# apex-alpha-ii.net
KiCad netlist of a schematic drawn in EAGLE
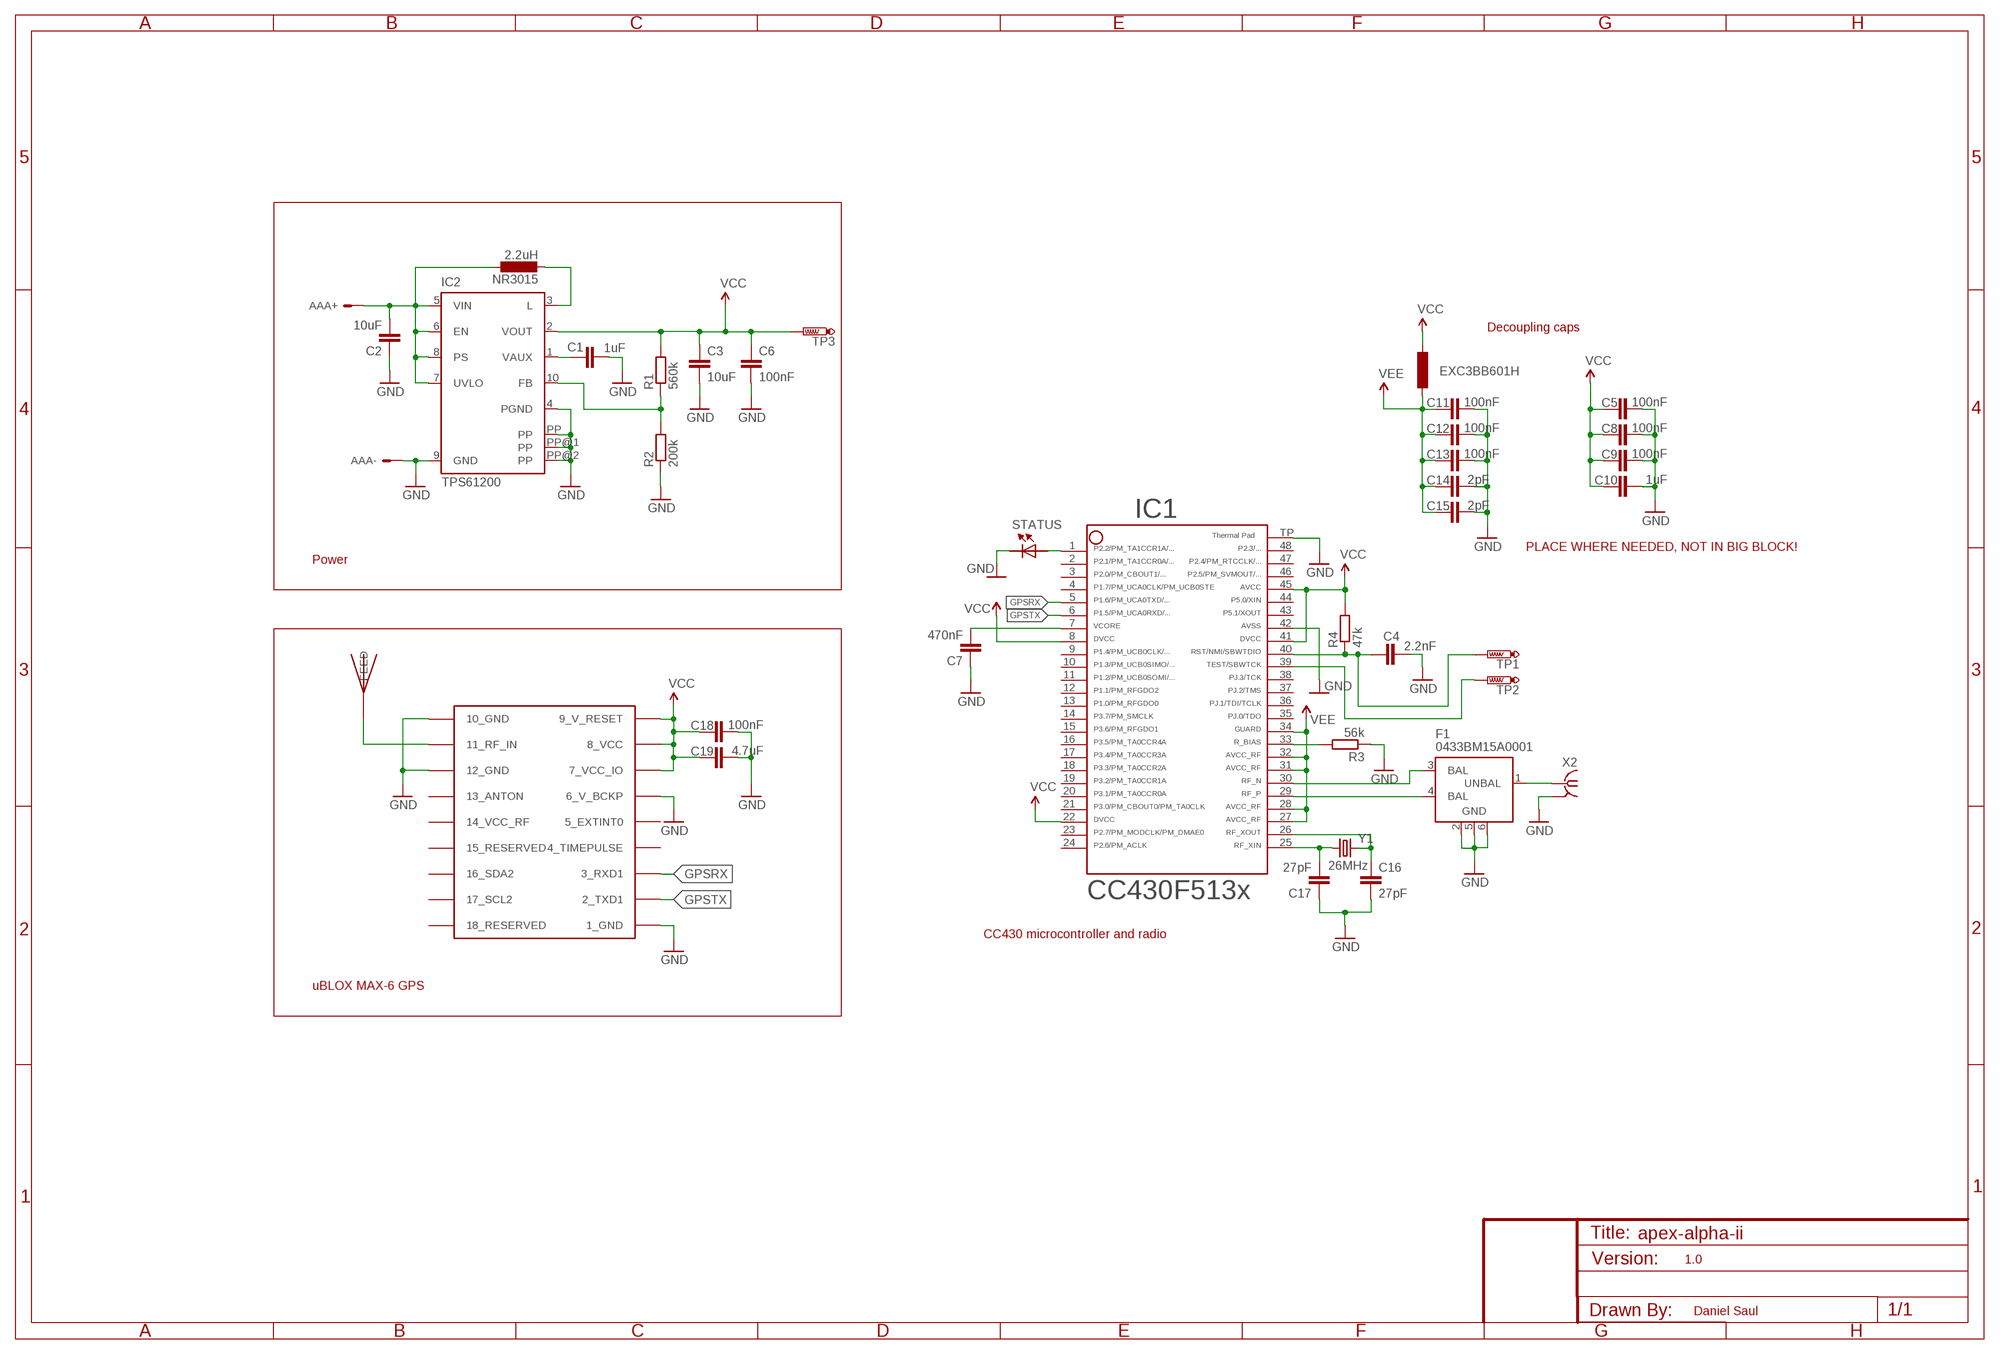
[diagram p0: schematic, sheet 1]

(export (version "E")
  (design (tool "Eeschema 10.0.6"))
  (components
    (comp (ref "AAA")
      (value "KEYSTONE-2466-THROUGH-HOLE-BATTERY-HOLDER-AAA")
      (footprint "eagle-import:THROUGH-HOLE-BATTERY-HOLDER-AAA")
      (libsource (lib "eagle-import") (part "KEYSTONE-2466-THROUGH-HOLE-BATTERY-HOLDER-AAA"))
    )
    (comp (ref "C1")
      (value "1uF")
      (footprint "eagle-import:0402-CAP")
      (libsource (lib "eagle-import") (part "CAP0402-CAP"))
    )
    (comp (ref "C2")
      (value "10uF")
      (footprint "eagle-import:0805")
      (libsource (lib "eagle-import") (part "CAP0805"))
    )
    (comp (ref "C3")
      (value "10uF")
      (footprint "eagle-import:0805")
      (libsource (lib "eagle-import") (part "CAP0805"))
    )
    (comp (ref "C4")
      (value "2.2nF")
      (footprint "eagle-import:0402-CAP")
      (libsource (lib "eagle-import") (part "CAP0402-CAP"))
    )
    (comp (ref "C5")
      (value "100nF")
      (footprint "eagle-import:0402-CAP")
      (libsource (lib "eagle-import") (part "CAP0402-CAP"))
    )
    (comp (ref "C6")
      (value "100nF")
      (footprint "eagle-import:0402-CAP")
      (libsource (lib "eagle-import") (part "CAP0402-CAP"))
    )
    (comp (ref "C7")
      (value "470nF")
      (footprint "eagle-import:0402-CAP")
      (libsource (lib "eagle-import") (part "CAP0402-CAP"))
    )
    (comp (ref "C8")
      (value "100nF")
      (footprint "eagle-import:0402-CAP")
      (libsource (lib "eagle-import") (part "CAP0402-CAP"))
    )
    (comp (ref "C9")
      (value "100nF")
      (footprint "eagle-import:0402-CAP")
      (libsource (lib "eagle-import") (part "CAP0402-CAP"))
    )
    (comp (ref "C10")
      (value "1uF")
      (footprint "eagle-import:0402-CAP")
      (libsource (lib "eagle-import") (part "CAP0402-CAP"))
    )
    (comp (ref "C11")
      (value "100nF")
      (footprint "eagle-import:0402-CAP")
      (libsource (lib "eagle-import") (part "CAP0402-CAP"))
    )
    (comp (ref "C12")
      (value "100nF")
      (footprint "eagle-import:0402-CAP")
      (libsource (lib "eagle-import") (part "CAP0402-CAP"))
    )
    (comp (ref "C13")
      (value "100nF")
      (footprint "eagle-import:0402-CAP")
      (libsource (lib "eagle-import") (part "CAP0402-CAP"))
    )
    (comp (ref "C14")
      (value "2pF")
      (footprint "eagle-import:0402-CAP")
      (libsource (lib "eagle-import") (part "CAP0402-CAP"))
    )
    (comp (ref "C15")
      (value "2pF")
      (footprint "eagle-import:0402-CAP")
      (libsource (lib "eagle-import") (part "CAP0402-CAP"))
    )
    (comp (ref "C16")
      (value "27pF")
      (footprint "eagle-import:0402-CAP")
      (libsource (lib "eagle-import") (part "CAP0402-CAP"))
    )
    (comp (ref "C17")
      (value "27pF")
      (footprint "eagle-import:0402-CAP")
      (libsource (lib "eagle-import") (part "CAP0402-CAP"))
    )
    (comp (ref "C18")
      (value "100nF")
      (footprint "eagle-import:0402-CAP")
      (libsource (lib "eagle-import") (part "CAP0402-CAP"))
    )
    (comp (ref "C19")
      (value "4.7uF")
      (footprint "eagle-import:0805")
      (libsource (lib "eagle-import") (part "CAP0805"))
    )
    (comp (ref "F1")
      (value "0433BM15A0001")
      (footprint "eagle-import:2450BM15A0002")
      (libsource (lib "eagle-import") (part "2450BM15A0002"))
    )
    (comp (ref "GPS")
      (value "UBLOX_MAX-6")
      (footprint "eagle-import:UBLOX_MAX-6")
      (libsource (lib "eagle-import") (part "UBLOX_MAX-6"))
    )
    (comp (ref "IC1")
      (value "CC430F5135")
      (footprint "eagle-import:RGZ48")
      (libsource (lib "eagle-import") (part "CC430F513X---RGZ48"))
    )
    (comp (ref "IC2")
      (value "TPS61200")
      (footprint "eagle-import:S-PDSO-N10")
      (fields (field (name "MPN") "TPS61200DRCT"))
      (libsource (lib "eagle-import") (part "TPS61200"))
    )
    (comp (ref "NR3015")
      (value "2.2uH")
      (footprint "eagle-import:NR3015")
      (libsource (lib "eagle-import") (part "NR3015"))
    )
    (comp (ref "R1")
      (value "560k")
      (footprint "eagle-import:R0402")
      (libsource (lib "eagle-import") (part "R-EU_R0402"))
    )
    (comp (ref "R2")
      (value "200k")
      (footprint "eagle-import:R0402")
      (libsource (lib "eagle-import") (part "R-EU_R0402"))
    )
    (comp (ref "R3")
      (value "56k")
      (footprint "eagle-import:R0402")
      (libsource (lib "eagle-import") (part "R-EU_R0402"))
    )
    (comp (ref "R4")
      (value "47k")
      (footprint "eagle-import:R0402")
      (libsource (lib "eagle-import") (part "R-EU_R0402"))
    )
    (comp (ref "TP1")
      (value "PTR1B1,27")
      (footprint "eagle-import:B1,27")
      (libsource (lib "eagle-import") (part "PTR1B1,27"))
    )
    (comp (ref "TP2")
      (value "PTR1B1,27")
      (footprint "eagle-import:B1,27")
      (libsource (lib "eagle-import") (part "PTR1B1,27"))
    )
    (comp (ref "TP3")
      (value "PTR1B1,27")
      (footprint "eagle-import:B1,27")
      (libsource (lib "eagle-import") (part "PTR1B1,27"))
    )
    (comp (ref "U$1")
      (value "JTI_ANTENNA-1575AT43A40")
      (footprint "eagle-import:JTI_ANTENNA-1575AT43A40")
      (libsource (lib "eagle-import") (part "JTI_ANTENNA-1575AT43A40"))
    )
    (comp (ref "U$2")
      (value "EXC3BB601H")
      (footprint "eagle-import:R0603")
      (libsource (lib "eagle-import") (part "0603INDUCTOR"))
    )
    (comp (ref "U$3")
      (value "STATUS")
      (footprint "eagle-import:R0402")
      (libsource (lib "eagle-import") (part "LED"))
    )
    (comp (ref "X2")
      (value "SMA-142-0701-801/806")
      (footprint "eagle-import:J502-ND-142-0701-801_806")
      (fields
        (field (name "MF") "JOHNSON COMPONENTS")
        (field (name "MPN") "142-0701-801")
        (field (name "MPN_1") "142-0701-801")
        (field (name "OC_FARNELL") "1608592")
        (field (name "OC_NEWARK") "90F2624")
      )
      (libsource (lib "eagle-import") (part "SMA-142-0701-801/806"))
    )
    (comp (ref "Y1")
      (value "26MHz")
      (footprint "eagle-import:CRYSTAL-SMD-5X3")
      (libsource (lib "eagle-import") (part "CRYSTAL5X3"))
    )
  )
  (nets
    (net (code "1") (name "GND") (class "Default")
      (node (ref "AAA") (pin "GND") (pinfunction "S_GND") (pintype "passive"))
      (node (ref "C1") (pin "2") (pinfunction "2_2") (pintype "passive"))
      (node (ref "C10") (pin "2") (pinfunction "2_2") (pintype "passive"))
      (node (ref "C11") (pin "2") (pinfunction "2_2") (pintype "passive"))
      (node (ref "C12") (pin "2") (pinfunction "2_2") (pintype "passive"))
      (node (ref "C13") (pin "2") (pinfunction "2_2") (pintype "passive"))
      (node (ref "C14") (pin "2") (pinfunction "2_2") (pintype "passive"))
      (node (ref "C15") (pin "2") (pinfunction "2_2") (pintype "passive"))
      (node (ref "C16") (pin "2") (pinfunction "2_2") (pintype "passive"))
      (node (ref "C17") (pin "1") (pinfunction "1_1") (pintype "passive"))
      (node (ref "C18") (pin "2") (pinfunction "2_2") (pintype "passive"))
      (node (ref "C19") (pin "2") (pinfunction "2_2") (pintype "passive"))
      (node (ref "C2") (pin "1") (pinfunction "1_1") (pintype "passive"))
      (node (ref "C3") (pin "2") (pinfunction "2_2") (pintype "passive"))
      (node (ref "C4") (pin "2") (pinfunction "2_2") (pintype "passive"))
      (node (ref "C5") (pin "2") (pinfunction "2_2") (pintype "passive"))
      (node (ref "C6") (pin "2") (pinfunction "2_2") (pintype "passive"))
      (node (ref "C7") (pin "1") (pinfunction "1_1") (pintype "passive"))
      (node (ref "C8") (pin "2") (pinfunction "2_2") (pintype "passive"))
      (node (ref "C9") (pin "2") (pinfunction "2_2") (pintype "passive"))
      (node (ref "F1") (pin "2") (pinfunction "GND_2") (pintype "passive"))
      (node (ref "F1") (pin "5") (pinfunction "GND_5") (pintype "passive"))
      (node (ref "F1") (pin "6") (pinfunction "GND_6") (pintype "passive"))
      (node (ref "GPS") (pin "10_GND") (pinfunction "10_GND_10_GND") (pintype "power_in"))
      (node (ref "GPS") (pin "12_GND") (pinfunction "12_GND_12_GND") (pintype "power_in"))
      (node (ref "GPS") (pin "1_GND") (pinfunction "1_GND_1_GND") (pintype "power_in"))
      (node (ref "GPS") (pin "6_V_BCKP") (pinfunction "6_V_BCKP_6_V_BCKP") (pintype "bidirectional"))
      (node (ref "IC1") (pin "42") (pinfunction "42_42") (pintype "power_in"))
      (node (ref "IC1") (pin "TP") (pinfunction "49_TP") (pintype "power_in"))
      (node (ref "IC2") (pin "4") (pinfunction "PGND_4") (pintype "power_in"))
      (node (ref "IC2") (pin "9") (pinfunction "GND_9") (pintype "power_in"))
      (node (ref "IC2") (pin "PP") (pinfunction "PP_PP") (pintype "power_in"))
      (node (ref "IC2") (pin "PP@1") (pinfunction "PP_PP@1") (pintype "power_in"))
      (node (ref "IC2") (pin "PP@2") (pinfunction "PP_PP@2") (pintype "power_in"))
      (node (ref "R2") (pin "1") (pinfunction "1_1") (pintype "passive"))
      (node (ref "R3") (pin "1") (pinfunction "1_1") (pintype "passive"))
      (node (ref "U$3") (pin "1") (pinfunction "C_1") (pintype "passive"))
      (node (ref "X2") (pin "G@1") (pinfunction "GND_G@1") (pintype "power_in"))
    )
    (net (code "2") (name "GPSRX") (class "Default")
      (node (ref "GPS") (pin "3_RXD1") (pinfunction "3_RXD1_3_RXD1") (pintype "bidirectional"))
      (node (ref "IC1") (pin "5") (pinfunction "5_5") (pintype "bidirectional"))
    )
    (net (code "3") (name "GPSTX") (class "Default")
      (node (ref "GPS") (pin "2_TXD1") (pinfunction "2_TXD1_2_TXD1") (pintype "bidirectional"))
      (node (ref "IC1") (pin "6") (pinfunction "6_6") (pintype "bidirectional"))
    )
    (net (code "4") (name "Net-(AAAA-S)") (class "Default")
      (node (ref "AAA") (pin "+V") (pinfunction "S_+V") (pintype "passive"))
      (node (ref "C2") (pin "2") (pinfunction "2_2") (pintype "passive"))
      (node (ref "IC2") (pin "5") (pinfunction "VIN_5") (pintype "input"))
      (node (ref "IC2") (pin "6") (pinfunction "EN_6") (pintype "input"))
      (node (ref "IC2") (pin "7") (pinfunction "UVLO_7") (pintype "input"))
      (node (ref "IC2") (pin "8") (pinfunction "PS_8") (pintype "input"))
      (node (ref "NR3015") (pin "P$1") (pinfunction "1_P$1") (pintype "passive"))
    )
    (net (code "5") (name "Net-(C4-Pad1)") (class "Default")
      (node (ref "C4") (pin "1") (pinfunction "1_1") (pintype "passive"))
      (node (ref "IC1") (pin "40") (pinfunction "40_40") (pintype "bidirectional"))
      (node (ref "R4") (pin "1") (pinfunction "1_1") (pintype "passive"))
      (node (ref "TP1") (pin "TP") (pinfunction "TP_TP") (pintype "input"))
    )
    (net (code "6") (name "Net-(C7-Pad2)") (class "Default")
      (node (ref "C7") (pin "2") (pinfunction "2_2") (pintype "passive"))
      (node (ref "IC1") (pin "7") (pinfunction "7_7") (pintype "power_in"))
    )
    (net (code "7") (name "Net-(C17-Pad2)") (class "Default")
      (node (ref "C17") (pin "2") (pinfunction "2_2") (pintype "passive"))
      (node (ref "IC1") (pin "25") (pinfunction "25_25") (pintype "input"))
      (node (ref "Y1") (pin "1") (pinfunction "1_1") (pintype "passive"))
    )
    (net (code "8") (name "Net-(F1-BAL-Pad3)") (class "Default")
      (node (ref "F1") (pin "3") (pinfunction "BAL_3") (pintype "passive"))
      (node (ref "IC1") (pin "30") (pinfunction "30_30") (pintype "bidirectional"))
    )
    (net (code "9") (name "Net-(F1-BAL-Pad4)") (class "Default")
      (node (ref "F1") (pin "4") (pinfunction "BAL_4") (pintype "passive"))
      (node (ref "IC1") (pin "29") (pinfunction "29_29") (pintype "bidirectional"))
    )
    (net (code "10") (name "Net-(F1-UNBAL)") (class "Default")
      (node (ref "F1") (pin "1") (pinfunction "UNBAL_1") (pintype "passive"))
      (node (ref "X2") (pin "1") (pinfunction "1_1") (pintype "passive"))
    )
    (net (code "11") (name "Net-(GPS-Pad11_RF_IN)") (class "Default")
      (node (ref "GPS") (pin "11_RF_IN") (pinfunction "11_RF_IN_11_RF_IN") (pintype "bidirectional"))
      (node (ref "U$1") (pin "FEED") (pinfunction "FEED_FEED") (pintype "bidirectional"))
    )
    (net (code "12") (name "Net-(IC1-Pad33)") (class "Default")
      (node (ref "IC1") (pin "33") (pinfunction "33_33") (pintype "power_in"))
      (node (ref "R3") (pin "2") (pinfunction "2_2") (pintype "passive"))
    )
    (net (code "13") (name "Net-(IC1-Pad39)") (class "Default")
      (node (ref "IC1") (pin "39") (pinfunction "39_39") (pintype "input"))
      (node (ref "TP2") (pin "TP") (pinfunction "TP_TP") (pintype "input"))
    )
    (net (code "14") (name "Net-(IC2-FB)") (class "Default")
      (node (ref "IC2") (pin "10") (pinfunction "FB_10") (pintype "input"))
      (node (ref "R1") (pin "1") (pinfunction "1_1") (pintype "passive"))
      (node (ref "R2") (pin "2") (pinfunction "2_2") (pintype "passive"))
    )
    (net (code "15") (name "Net-(IC2-L)") (class "Default")
      (node (ref "IC2") (pin "3") (pinfunction "L_3") (pintype "input"))
      (node (ref "NR3015") (pin "P$2") (pinfunction "2_P$2") (pintype "passive"))
    )
    (net (code "16") (name "Net-(IC2-VAUX)") (class "Default")
      (node (ref "C1") (pin "1") (pinfunction "1_1") (pintype "passive"))
      (node (ref "IC2") (pin "1") (pinfunction "VAUX_1") (pintype "bidirectional"))
    )
    (net (code "17") (name "Net-(U$3-A)") (class "Default")
      (node (ref "IC1") (pin "1") (pinfunction "1_1") (pintype "bidirectional"))
      (node (ref "U$3") (pin "2") (pinfunction "A_2") (pintype "passive"))
    )
    (net (code "18") (name "Net-(Y1-2)") (class "Default")
      (node (ref "C16") (pin "1") (pinfunction "1_1") (pintype "passive"))
      (node (ref "IC1") (pin "26") (pinfunction "26_26") (pintype "output"))
      (node (ref "Y1") (pin "3") (pinfunction "2_3") (pintype "passive"))
    )
    (net (code "19") (name "VCC") (class "Default")
      (node (ref "C10") (pin "1") (pinfunction "1_1") (pintype "passive"))
      (node (ref "C18") (pin "1") (pinfunction "1_1") (pintype "passive"))
      (node (ref "C19") (pin "1") (pinfunction "1_1") (pintype "passive"))
      (node (ref "C3") (pin "1") (pinfunction "1_1") (pintype "passive"))
      (node (ref "C5") (pin "1") (pinfunction "1_1") (pintype "passive"))
      (node (ref "C6") (pin "1") (pinfunction "1_1") (pintype "passive"))
      (node (ref "C8") (pin "1") (pinfunction "1_1") (pintype "passive"))
      (node (ref "C9") (pin "1") (pinfunction "1_1") (pintype "passive"))
      (node (ref "GPS") (pin "7_VCC_IO") (pinfunction "7_VCC_IO_7_VCC_IO") (pintype "power_in"))
      (node (ref "GPS") (pin "8_VCC") (pinfunction "8_VCC_8_VCC") (pintype "power_in"))
      (node (ref "GPS") (pin "9_V_RESET") (pinfunction "9_V_RESET_9_V_RESET") (pintype "power_in"))
      (node (ref "IC1") (pin "22") (pinfunction "22_22") (pintype "power_in"))
      (node (ref "IC1") (pin "41") (pinfunction "41_41") (pintype "power_in"))
      (node (ref "IC1") (pin "45") (pinfunction "45_45") (pintype "input"))
      (node (ref "IC1") (pin "8") (pinfunction "8_8") (pintype "power_in"))
      (node (ref "IC2") (pin "2") (pinfunction "VOUT_2") (pintype "passive"))
      (node (ref "R1") (pin "2") (pinfunction "2_2") (pintype "passive"))
      (node (ref "R4") (pin "2") (pinfunction "2_2") (pintype "passive"))
      (node (ref "TP3") (pin "TP") (pinfunction "TP_TP") (pintype "input"))
      (node (ref "U$2") (pin "1") (pinfunction "1_1") (pintype "passive"))
    )
    (net (code "20") (name "VEE") (class "Default")
      (node (ref "C11") (pin "1") (pinfunction "1_1") (pintype "passive"))
      (node (ref "C12") (pin "1") (pinfunction "1_1") (pintype "passive"))
      (node (ref "C13") (pin "1") (pinfunction "1_1") (pintype "passive"))
      (node (ref "C14") (pin "1") (pinfunction "1_1") (pintype "passive"))
      (node (ref "C15") (pin "1") (pinfunction "1_1") (pintype "passive"))
      (node (ref "IC1") (pin "27") (pinfunction "27_27") (pintype "power_in"))
      (node (ref "IC1") (pin "28") (pinfunction "28_28") (pintype "bidirectional"))
      (node (ref "IC1") (pin "31") (pinfunction "31_31") (pintype "power_in"))
      (node (ref "IC1") (pin "32") (pinfunction "32_32") (pintype "power_in"))
      (node (ref "IC1") (pin "34") (pinfunction "34_34") (pintype "power_in"))
      (node (ref "U$2") (pin "2") (pinfunction "2_2") (pintype "passive"))
    )
    (net (code "21") (name "unconnected-(GPS-Pad4_TIMEPULSE)") (class "Default")
      (node (ref "GPS") (pin "4_TIMEPULSE") (pinfunction "4_TIMEPULSE_4_TIMEPULSE") (pintype "bidirectional"))
    )
    (net (code "22") (name "unconnected-(GPS-Pad5_EXTINT0)") (class "Default")
      (node (ref "GPS") (pin "5_EXTINT0") (pinfunction "5_EXTINT0_5_EXTINT0") (pintype "bidirectional"))
    )
    (net (code "23") (name "unconnected-(GPS-Pad13_ANTON)") (class "Default")
      (node (ref "GPS") (pin "13_ANTON") (pinfunction "13_ANTON_13_ANTON") (pintype "bidirectional"))
    )
    (net (code "24") (name "unconnected-(GPS-Pad14_VCC_RF)") (class "Default")
      (node (ref "GPS") (pin "14_VCC_RF") (pinfunction "14_VCC_RF_14_VCC_RF") (pintype "bidirectional"))
    )
    (net (code "25") (name "unconnected-(GPS-Pad15_RESERVED)") (class "Default")
      (node (ref "GPS") (pin "15_RESERVED") (pinfunction "15_RESERVED_15_RESERVED") (pintype "bidirectional"))
    )
    (net (code "26") (name "unconnected-(GPS-Pad16_SDA2)") (class "Default")
      (node (ref "GPS") (pin "16_SDA2") (pinfunction "16_SDA2_16_SDA2") (pintype "bidirectional"))
    )
    (net (code "27") (name "unconnected-(GPS-Pad17_SCL2)") (class "Default")
      (node (ref "GPS") (pin "17_SCL2") (pinfunction "17_SCL2_17_SCL2") (pintype "bidirectional"))
    )
    (net (code "28") (name "unconnected-(GPS-Pad18_RESERVED)") (class "Default")
      (node (ref "GPS") (pin "18_RESERVED") (pinfunction "18_RESERVED_18_RESERVED") (pintype "bidirectional"))
    )
    (net (code "29") (name "unconnected-(IC1-Pad2)") (class "Default")
      (node (ref "IC1") (pin "2") (pinfunction "2_2") (pintype "bidirectional"))
    )
    (net (code "30") (name "unconnected-(IC1-Pad3)") (class "Default")
      (node (ref "IC1") (pin "3") (pinfunction "3_3") (pintype "bidirectional"))
    )
    (net (code "31") (name "unconnected-(IC1-Pad4)") (class "Default")
      (node (ref "IC1") (pin "4") (pinfunction "4_4") (pintype "bidirectional"))
    )
    (net (code "32") (name "unconnected-(IC1-Pad9)") (class "Default")
      (node (ref "IC1") (pin "9") (pinfunction "9_9") (pintype "bidirectional"))
    )
    (net (code "33") (name "unconnected-(IC1-Pad10)") (class "Default")
      (node (ref "IC1") (pin "10") (pinfunction "10_10") (pintype "bidirectional"))
    )
    (net (code "34") (name "unconnected-(IC1-Pad11)") (class "Default")
      (node (ref "IC1") (pin "11") (pinfunction "11_11") (pintype "bidirectional"))
    )
    (net (code "35") (name "unconnected-(IC1-Pad12)") (class "Default")
      (node (ref "IC1") (pin "12") (pinfunction "12_12") (pintype "bidirectional"))
    )
    (net (code "36") (name "unconnected-(IC1-Pad13)") (class "Default")
      (node (ref "IC1") (pin "13") (pinfunction "13_13") (pintype "bidirectional"))
    )
    (net (code "37") (name "unconnected-(IC1-Pad14)") (class "Default")
      (node (ref "IC1") (pin "14") (pinfunction "14_14") (pintype "bidirectional"))
    )
    (net (code "38") (name "unconnected-(IC1-Pad15)") (class "Default")
      (node (ref "IC1") (pin "15") (pinfunction "15_15") (pintype "bidirectional"))
    )
    (net (code "39") (name "unconnected-(IC1-Pad16)") (class "Default")
      (node (ref "IC1") (pin "16") (pinfunction "16_16") (pintype "bidirectional"))
    )
    (net (code "40") (name "unconnected-(IC1-Pad17)") (class "Default")
      (node (ref "IC1") (pin "17") (pinfunction "17_17") (pintype "bidirectional"))
    )
    (net (code "41") (name "unconnected-(IC1-Pad18)") (class "Default")
      (node (ref "IC1") (pin "18") (pinfunction "18_18") (pintype "bidirectional"))
    )
    (net (code "42") (name "unconnected-(IC1-Pad19)") (class "Default")
      (node (ref "IC1") (pin "19") (pinfunction "19_19") (pintype "bidirectional"))
    )
    (net (code "43") (name "unconnected-(IC1-Pad20)") (class "Default")
      (node (ref "IC1") (pin "20") (pinfunction "20_20") (pintype "bidirectional"))
    )
    (net (code "44") (name "unconnected-(IC1-Pad21)") (class "Default")
      (node (ref "IC1") (pin "21") (pinfunction "21_21") (pintype "bidirectional"))
    )
    (net (code "45") (name "unconnected-(IC1-Pad23)") (class "Default")
      (node (ref "IC1") (pin "23") (pinfunction "23_23") (pintype "bidirectional"))
    )
    (net (code "46") (name "unconnected-(IC1-Pad24)") (class "Default")
      (node (ref "IC1") (pin "24") (pinfunction "24_24") (pintype "bidirectional"))
    )
    (net (code "47") (name "unconnected-(IC1-Pad35)") (class "Default")
      (node (ref "IC1") (pin "35") (pinfunction "35_35") (pintype "bidirectional"))
    )
    (net (code "48") (name "unconnected-(IC1-Pad36)") (class "Default")
      (node (ref "IC1") (pin "36") (pinfunction "36_36") (pintype "bidirectional"))
    )
    (net (code "49") (name "unconnected-(IC1-Pad37)") (class "Default")
      (node (ref "IC1") (pin "37") (pinfunction "37_37") (pintype "bidirectional"))
    )
    (net (code "50") (name "unconnected-(IC1-Pad38)") (class "Default")
      (node (ref "IC1") (pin "38") (pinfunction "38_38") (pintype "bidirectional"))
    )
    (net (code "51") (name "unconnected-(IC1-Pad43)") (class "Default")
      (node (ref "IC1") (pin "43") (pinfunction "43_43") (pintype "input"))
    )
    (net (code "52") (name "unconnected-(IC1-Pad44)") (class "Default")
      (node (ref "IC1") (pin "44") (pinfunction "44_44") (pintype "input"))
    )
    (net (code "53") (name "unconnected-(IC1-Pad46)") (class "Default")
      (node (ref "IC1") (pin "46") (pinfunction "46_46") (pintype "bidirectional"))
    )
    (net (code "54") (name "unconnected-(IC1-Pad47)") (class "Default")
      (node (ref "IC1") (pin "47") (pinfunction "47_47") (pintype "input"))
    )
    (net (code "55") (name "unconnected-(IC1-Pad48)") (class "Default")
      (node (ref "IC1") (pin "48") (pinfunction "48_48") (pintype "bidirectional"))
    )
  )
)
